# P6F.net
KiCad netlist of a schematic drawn in EAGLE
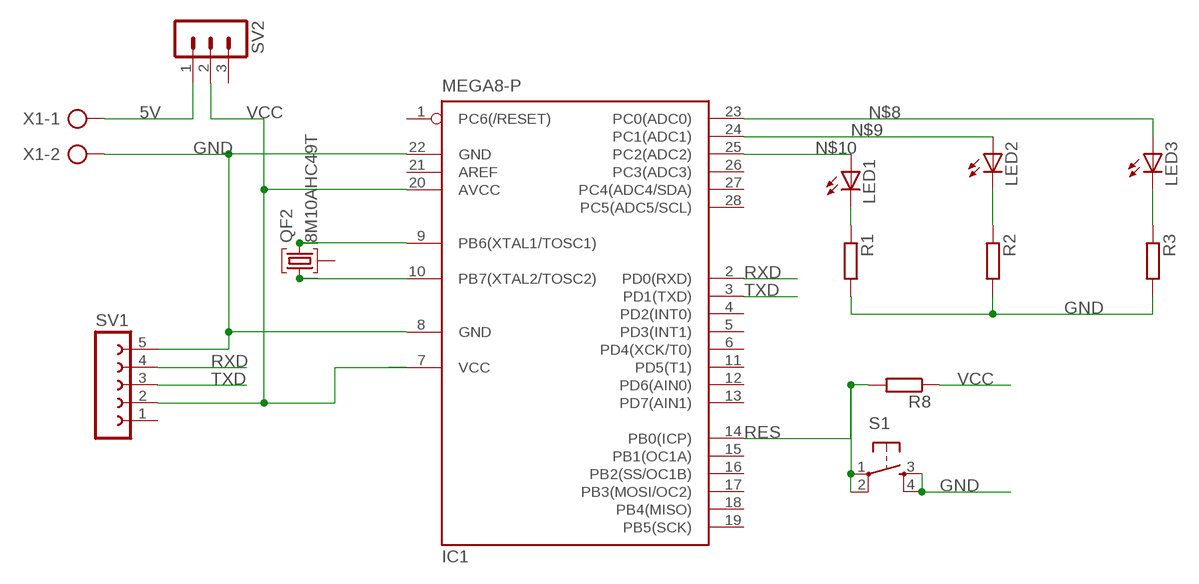
[diagram p0: schematic, sheet 1]

(export (version "E")
  (design (tool "Eeschema 10.0.6"))
  (components
    (comp (ref "IC1")
      (value "MEGA8-P")
      (footprint "eagle-import:DIL28-3")
      (libsource (lib "eagle-import") (part "MEGA8-P"))
    )
    (comp (ref "LED1")
      (value "LED5MM")
      (footprint "eagle-import:LED5MM")
      (libsource (lib "eagle-import") (part "LED5MM"))
    )
    (comp (ref "LED2")
      (value "LED5MM")
      (footprint "eagle-import:LED5MM")
      (libsource (lib "eagle-import") (part "LED5MM"))
    )
    (comp (ref "LED3")
      (value "LED5MM")
      (footprint "eagle-import:LED5MM")
      (libsource (lib "eagle-import") (part "LED5MM"))
    )
    (comp (ref "QF2")
      (value "8M10AHC49T")
      (footprint "eagle-import:HC49U")
      (libsource (lib "eagle-import") (part "8M10AHC49T"))
    )
    (comp (ref "R1")
      (value "R-EU_0204/7")
      (footprint "eagle-import:0204_7")
      (libsource (lib "eagle-import") (part "R-EU_0204/7"))
    )
    (comp (ref "R2")
      (value "R-EU_0204/7")
      (footprint "eagle-import:0204_7")
      (libsource (lib "eagle-import") (part "R-EU_0204/7"))
    )
    (comp (ref "R3")
      (value "R-EU_0204/7")
      (footprint "eagle-import:0204_7")
      (libsource (lib "eagle-import") (part "R-EU_0204/7"))
    )
    (comp (ref "R8")
      (value "R-EU_0204/7")
      (footprint "eagle-import:0204_7")
      (libsource (lib "eagle-import") (part "R-EU_0204/7"))
    )
    (comp (ref "S1")
      (value "TAC_SWITCHPTH")
      (footprint "eagle-import:TACTILE-PTH")
      (libsource (lib "eagle-import") (part "TAC_SWITCHPTH"))
    )
    (comp (ref "SV1")
      (value "FE05-1")
      (footprint "eagle-import:FE05-1")
      (libsource (lib "eagle-import") (part "FE05-1"))
    )
    (comp (ref "SV2")
      (value "MA03-1")
      (footprint "eagle-import:MA03-1")
      (libsource (lib "eagle-import") (part "MA03-1"))
    )
    (comp (ref "X1")
      (value "AK300/2")
      (footprint "eagle-import:AK300_2")
      (libsource (lib "eagle-import") (part "AK300/2"))
    )
  )
  (nets
    (net (code "1") (name "/5V") (class "Default")
      (node (ref "SV2") (pin "1") (pinfunction "1_1") (pintype "passive"))
      (node (ref "X1") (pin "1") (pinfunction "KL_1") (pintype "passive"))
    )
    (net (code "2") (name "/GND") (class "Default")
      (node (ref "IC1") (pin "22") (pinfunction "GND_22") (pintype "power_in"))
      (node (ref "IC1") (pin "8") (pinfunction "GND_8") (pintype "power_in"))
      (node (ref "R1") (pin "2") (pinfunction "2_2") (pintype "passive"))
      (node (ref "R2") (pin "2") (pinfunction "2_2") (pintype "passive"))
      (node (ref "R3") (pin "2") (pinfunction "2_2") (pintype "passive"))
      (node (ref "S1") (pin "3") (pinfunction "3_3") (pintype "passive"))
      (node (ref "S1") (pin "4") (pinfunction "4_4") (pintype "passive"))
      (node (ref "SV1") (pin "5") (pinfunction "5_5") (pintype "passive"))
      (node (ref "X1") (pin "2") (pinfunction "KL_2") (pintype "passive"))
    )
    (net (code "3") (name "/N$8") (class "Default")
      (node (ref "IC1") (pin "23") (pinfunction "PC0(ADC0)_23") (pintype "bidirectional"))
      (node (ref "LED3") (pin "A") (pinfunction "A_A") (pintype "passive"))
    )
    (net (code "4") (name "/N$9") (class "Default")
      (node (ref "IC1") (pin "24") (pinfunction "PC1(ADC1)_24") (pintype "bidirectional"))
      (node (ref "LED2") (pin "A") (pinfunction "A_A") (pintype "passive"))
    )
    (net (code "5") (name "/N$10") (class "Default")
      (node (ref "IC1") (pin "25") (pinfunction "PC2(ADC2)_25") (pintype "bidirectional"))
      (node (ref "LED1") (pin "A") (pinfunction "A_A") (pintype "passive"))
    )
    (net (code "6") (name "/RES") (class "Default")
      (node (ref "IC1") (pin "14") (pinfunction "PB0(ICP)_14") (pintype "bidirectional"))
      (node (ref "R8") (pin "2") (pinfunction "2_2") (pintype "passive"))
      (node (ref "S1") (pin "1") (pinfunction "1_1") (pintype "passive"))
      (node (ref "S1") (pin "2") (pinfunction "2_2") (pintype "passive"))
    )
    (net (code "7") (name "/RXD") (class "Default")
      (node (ref "IC1") (pin "2") (pinfunction "PD0(RXD)_2") (pintype "bidirectional"))
      (node (ref "SV1") (pin "4") (pinfunction "4_4") (pintype "passive"))
    )
    (net (code "8") (name "/TXD") (class "Default")
      (node (ref "IC1") (pin "3") (pinfunction "PD1(TXD)_3") (pintype "bidirectional"))
      (node (ref "SV1") (pin "3") (pinfunction "3_3") (pintype "passive"))
    )
    (net (code "9") (name "/VCC") (class "Default")
      (node (ref "IC1") (pin "20") (pinfunction "AVCC_20") (pintype "power_in"))
      (node (ref "IC1") (pin "7") (pinfunction "VCC_7") (pintype "power_in"))
      (node (ref "R8") (pin "1") (pinfunction "1_1") (pintype "passive"))
      (node (ref "SV1") (pin "2") (pinfunction "2_2") (pintype "passive"))
      (node (ref "SV2") (pin "2") (pinfunction "2_2") (pintype "passive"))
    )
    (net (code "10") (name "Net-(IC1-PB6(XTAL1{slash}TOSC1))") (class "Default")
      (node (ref "IC1") (pin "9") (pinfunction "PB6(XTAL1/TOSC1)_9") (pintype "bidirectional"))
      (node (ref "QF2") (pin "3") (pinfunction "3_3") (pintype "passive"))
    )
    (net (code "11") (name "Net-(IC1-PB7(XTAL2{slash}TOSC2))") (class "Default")
      (node (ref "IC1") (pin "10") (pinfunction "PB7(XTAL2/TOSC2)_10") (pintype "bidirectional"))
      (node (ref "QF2") (pin "1") (pinfunction "1_1") (pintype "passive"))
    )
    (net (code "12") (name "Net-(LED1-C)") (class "Default")
      (node (ref "LED1") (pin "K") (pinfunction "C_K") (pintype "passive"))
      (node (ref "R1") (pin "1") (pinfunction "1_1") (pintype "passive"))
    )
    (net (code "13") (name "Net-(LED2-C)") (class "Default")
      (node (ref "LED2") (pin "K") (pinfunction "C_K") (pintype "passive"))
      (node (ref "R2") (pin "1") (pinfunction "1_1") (pintype "passive"))
    )
    (net (code "14") (name "Net-(LED3-C)") (class "Default")
      (node (ref "LED3") (pin "K") (pinfunction "C_K") (pintype "passive"))
      (node (ref "R3") (pin "1") (pinfunction "1_1") (pintype "passive"))
    )
    (net (code "15") (name "unconnected-(IC1-AREF-Pad21)") (class "Default")
      (node (ref "IC1") (pin "21") (pinfunction "AREF_21") (pintype "passive"))
    )
    (net (code "16") (name "unconnected-(IC1-PB1(OC1A)-Pad15)") (class "Default")
      (node (ref "IC1") (pin "15") (pinfunction "PB1(OC1A)_15") (pintype "bidirectional"))
    )
    (net (code "17") (name "unconnected-(IC1-PB2(SS{slash}OC1B)-Pad16)") (class "Default")
      (node (ref "IC1") (pin "16") (pinfunction "PB2(SS/OC1B)_16") (pintype "bidirectional"))
    )
    (net (code "18") (name "unconnected-(IC1-PB3(MOSI{slash}OC2)-Pad17)") (class "Default")
      (node (ref "IC1") (pin "17") (pinfunction "PB3(MOSI/OC2)_17") (pintype "bidirectional"))
    )
    (net (code "19") (name "unconnected-(IC1-PB4(MISO)-Pad18)") (class "Default")
      (node (ref "IC1") (pin "18") (pinfunction "PB4(MISO)_18") (pintype "bidirectional"))
    )
    (net (code "20") (name "unconnected-(IC1-PB5(SCK)-Pad19)") (class "Default")
      (node (ref "IC1") (pin "19") (pinfunction "PB5(SCK)_19") (pintype "bidirectional"))
    )
    (net (code "21") (name "unconnected-(IC1-PC3(ADC3)-Pad26)") (class "Default")
      (node (ref "IC1") (pin "26") (pinfunction "PC3(ADC3)_26") (pintype "bidirectional"))
    )
    (net (code "22") (name "unconnected-(IC1-PC4(ADC4{slash}SDA)-Pad27)") (class "Default")
      (node (ref "IC1") (pin "27") (pinfunction "PC4(ADC4/SDA)_27") (pintype "bidirectional"))
    )
    (net (code "23") (name "unconnected-(IC1-PC5(ADC5{slash}SCL)-Pad28)") (class "Default")
      (node (ref "IC1") (pin "28") (pinfunction "PC5(ADC5/SCL)_28") (pintype "bidirectional"))
    )
    (net (code "24") (name "unconnected-(IC1-PC6({slash}RESET)-Pad1)") (class "Default")
      (node (ref "IC1") (pin "1") (pinfunction "PC6(/RESET)_1") (pintype "bidirectional"))
    )
    (net (code "25") (name "unconnected-(IC1-PD2(INT0)-Pad4)") (class "Default")
      (node (ref "IC1") (pin "4") (pinfunction "PD2(INT0)_4") (pintype "bidirectional"))
    )
    (net (code "26") (name "unconnected-(IC1-PD3(INT1)-Pad5)") (class "Default")
      (node (ref "IC1") (pin "5") (pinfunction "PD3(INT1)_5") (pintype "bidirectional"))
    )
    (net (code "27") (name "unconnected-(IC1-PD4(XCK{slash}T0)-Pad6)") (class "Default")
      (node (ref "IC1") (pin "6") (pinfunction "PD4(XCK/T0)_6") (pintype "bidirectional"))
    )
    (net (code "28") (name "unconnected-(IC1-PD5(T1)-Pad11)") (class "Default")
      (node (ref "IC1") (pin "11") (pinfunction "PD5(T1)_11") (pintype "bidirectional"))
    )
    (net (code "29") (name "unconnected-(IC1-PD6(AIN0)-Pad12)") (class "Default")
      (node (ref "IC1") (pin "12") (pinfunction "PD6(AIN0)_12") (pintype "bidirectional"))
    )
    (net (code "30") (name "unconnected-(IC1-PD7(AIN1)-Pad13)") (class "Default")
      (node (ref "IC1") (pin "13") (pinfunction "PD7(AIN1)_13") (pintype "bidirectional"))
    )
    (net (code "31") (name "unconnected-(QF2-Pad2)") (class "Default")
      (node (ref "QF2") (pin "2") (pinfunction "2_2") (pintype "passive"))
    )
    (net (code "32") (name "unconnected-(SV1-Pad1)") (class "Default")
      (node (ref "SV1") (pin "1") (pinfunction "1_1") (pintype "passive"))
    )
    (net (code "33") (name "unconnected-(SV2-Pad3)") (class "Default")
      (node (ref "SV2") (pin "3") (pinfunction "3_3") (pintype "passive"))
    )
  )
)
